# 2W5_Audio_amp.net
KiCad netlist of a schematic drawn in Altium Designer
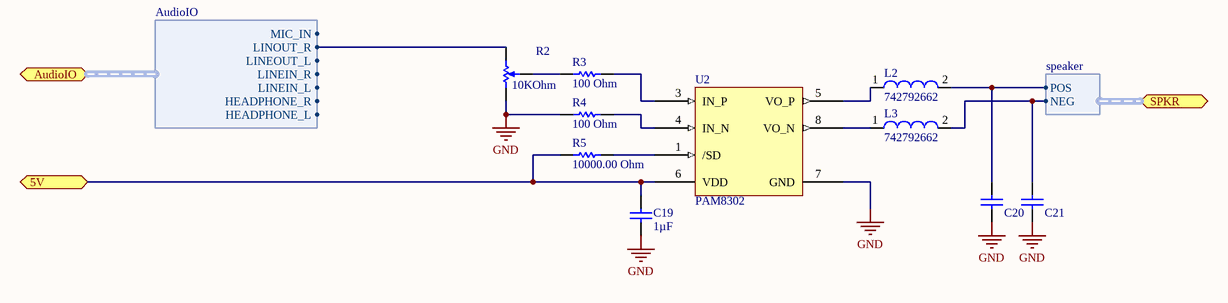
[diagram p0: 2W5_Audio_amp.SchDoc]

(export (version "E")
  (design (tool "Eeschema 10.0.6"))
  (components
    (comp (ref "C19")
      (value "C1005X5R1C105K050BC")
      (footprint "CAPC1005X55X10ML05")
      (description "Chip Capacitor, 1 uF, +/- 10%, 16 V, -55 to 85 degC, 0402 (1005 Metric), RoHS, Tape and Reel")
      (fields
        (field (name "TOLERANCE") "±10%")
        (field (name "CAPACITANCE") "1µF")
        (field (name "PCN PART NUMBER") "MLCCPartNumberChange30/Nov/2012")
      )
      (libsource (lib "Altium Content Vault") (part "CMP-2000-05003-1"))
    )
    (comp (ref "C20")
      (value "CAP 220pF 16V 0402(1005)")
      (footprint "CAPC0402(1005)60_N")
      (description "CAP 220pF 16V ±10% 0402 (1005 Metric) Thickness 0.6mm SMD")
      (fields (field (name "TOLERANCE") "Â±10%"))
      (libsource (lib "Altium Content Vault") (part "CMP-1034-01360-1"))
    )
    (comp (ref "C21")
      (value "CAP 220pF 16V 0402(1005)")
      (footprint "CAPC0402(1005)60_N")
      (description "CAP 220pF 16V ±10% 0402 (1005 Metric) Thickness 0.6mm SMD")
      (fields (field (name "TOLERANCE") "Â±10%"))
      (libsource (lib "Altium Content Vault") (part "CMP-1034-01360-1"))
    )
    (comp (ref "L2")
      (value "742792662")
      (footprint "SMD-0603")
      (description "SMD EMI Suppression Ferrite Bead WE-CBF, Z = 1000 Ohm")
      (libsource (lib "Altium Content Vault") (part "CMP-0220-00178-1"))
    )
    (comp (ref "L3")
      (value "742792662")
      (footprint "SMD-0603")
      (description "SMD EMI Suppression Ferrite Bead WE-CBF, Z = 1000 Ohm")
      (libsource (lib "Altium Content Vault") (part "CMP-0220-00178-1"))
    )
    (comp (ref "R2")
      (value "TC33X-2-103E")
      (footprint "BOUR-TC33X-2_V")
      (description "Trimming Potentiometer, 10000 Ohm, -40 to 100 degC, 3-Pin SMD, RoHS, Tape and Reel")
      (fields
        (field (name "TOLERANCE") "25%")
        (field (name "RESISTANCE") "10KOhm")
        (field (name "MANUFACTURER") "Bourns")
      )
      (libsource (lib "Altium Content Vault") (part "CMP-2100-03695-1"))
    )
    (comp (ref "R3")
      (value "100 Ohm")
      (footprint "RESC0402(1005)_N")
      (description "100 0.063W 5% 0402 (1005 Metric)  SMD")
      (fields (field (name "POWER") "0.063 W") (field (name "TOLERANCE") "5 %"))
      (libsource (lib "Altium Content Vault") (part "CMP-1011-00081-1"))
    )
    (comp (ref "R4")
      (value "100 Ohm")
      (footprint "RESC0402(1005)_N")
      (description "100 0.063W 5% 0402 (1005 Metric)  SMD")
      (fields (field (name "POWER") "0.063 W") (field (name "TOLERANCE") "5 %"))
      (libsource (lib "Altium Content Vault") (part "CMP-1011-00081-1"))
    )
    (comp (ref "R5")
      (value "10000.00 Ohm")
      (footprint "RESC0402(1005)_N")
      (description "10K 0.063W 5% 0402 (1005 Metric)  SMD")
      (fields (field (name "POWER") "0.063 W") (field (name "TOLERANCE") "5 %"))
      (libsource (lib "Altium Content Vault") (part "CMP-1011-00081-1"))
    )
    (comp (ref "U2")
      (value "PAM8302")
      (footprint "MSOP-8N")
      (fields (field (name "MANUFACTURER") "Diodes Incorporated"))
      (libsource (lib "PAM8302A") (part "Component_1"))
    )
  )
  (nets
    (net (code "3") (name "/5V") (class "Default")
      (node (ref "C19") (pin "1") (pinfunction "1_1") (pintype "passive"))
      (node (ref "R5") (pin "1") (pinfunction "1_1") (pintype "passive"))
      (node (ref "U2") (pin "6") (pinfunction "VDD_6") (pintype "power_in"))
    )
    (net (code "4") (name "/LINOUT_R") (class "Default")
      (node (ref "R2") (pin "3") (pinfunction "3_3") (pintype "passive"))
    )
    (net (code "5") (name "/NEG") (class "Default")
      (node (ref "C21") (pin "2") (pinfunction "2_2") (pintype "passive"))
      (node (ref "L3") (pin "2") (pinfunction "2_2") (pintype "passive"))
    )
    (net (code "6") (name "/POS") (class "Default")
      (node (ref "C20") (pin "2") (pinfunction "2_2") (pintype "passive"))
      (node (ref "L2") (pin "2") (pinfunction "2_2") (pintype "passive"))
    )
    (net (code "9") (name "GND") (class "Default")
      (node (ref "C19") (pin "2") (pinfunction "2_2") (pintype "passive"))
      (node (ref "C20") (pin "1") (pinfunction "1_1") (pintype "passive"))
      (node (ref "C21") (pin "1") (pinfunction "1_1") (pintype "passive"))
      (node (ref "R2") (pin "1") (pinfunction "1_1") (pintype "passive"))
      (node (ref "R4") (pin "1") (pinfunction "1_1") (pintype "passive"))
      (node (ref "U2") (pin "7") (pinfunction "GND_7") (pintype "power_in"))
    )
    (net (code "10") (name "Net-(R2-Pad2)") (class "Default")
      (node (ref "R2") (pin "2") (pinfunction "2_2") (pintype "passive"))
      (node (ref "R3") (pin "1") (pinfunction "1_1") (pintype "passive"))
    )
    (net (code "11") (name "Net-(U2-IN_N)") (class "Default")
      (node (ref "R4") (pin "2") (pinfunction "2_2") (pintype "passive"))
      (node (ref "U2") (pin "4") (pinfunction "IN_N_4") (pintype "input"))
    )
    (net (code "12") (name "Net-(U2-IN_P)") (class "Default")
      (node (ref "R3") (pin "2") (pinfunction "2_2") (pintype "passive"))
      (node (ref "U2") (pin "3") (pinfunction "IN_P_3") (pintype "input"))
    )
    (net (code "13") (name "Net-(U2-VO_N)") (class "Default")
      (node (ref "L3") (pin "1") (pinfunction "1_1") (pintype "passive"))
      (node (ref "U2") (pin "8") (pinfunction "VO_N_8") (pintype "output"))
    )
    (net (code "14") (name "Net-(U2-VO_P)") (class "Default")
      (node (ref "L2") (pin "1") (pinfunction "1_1") (pintype "passive"))
      (node (ref "U2") (pin "5") (pinfunction "VO_P_5") (pintype "output"))
    )
    (net (code "15") (name "Net-(U2-{slash}SD)") (class "Default")
      (node (ref "R5") (pin "2") (pinfunction "2_2") (pintype "passive"))
      (node (ref "U2") (pin "1") (pinfunction "/SD_1") (pintype "input"))
    )
  )
)
